# ProDoc_Schematic1_2025-12-06_1.net
KiCad netlist of a schematic drawn in EasyEDA Pro
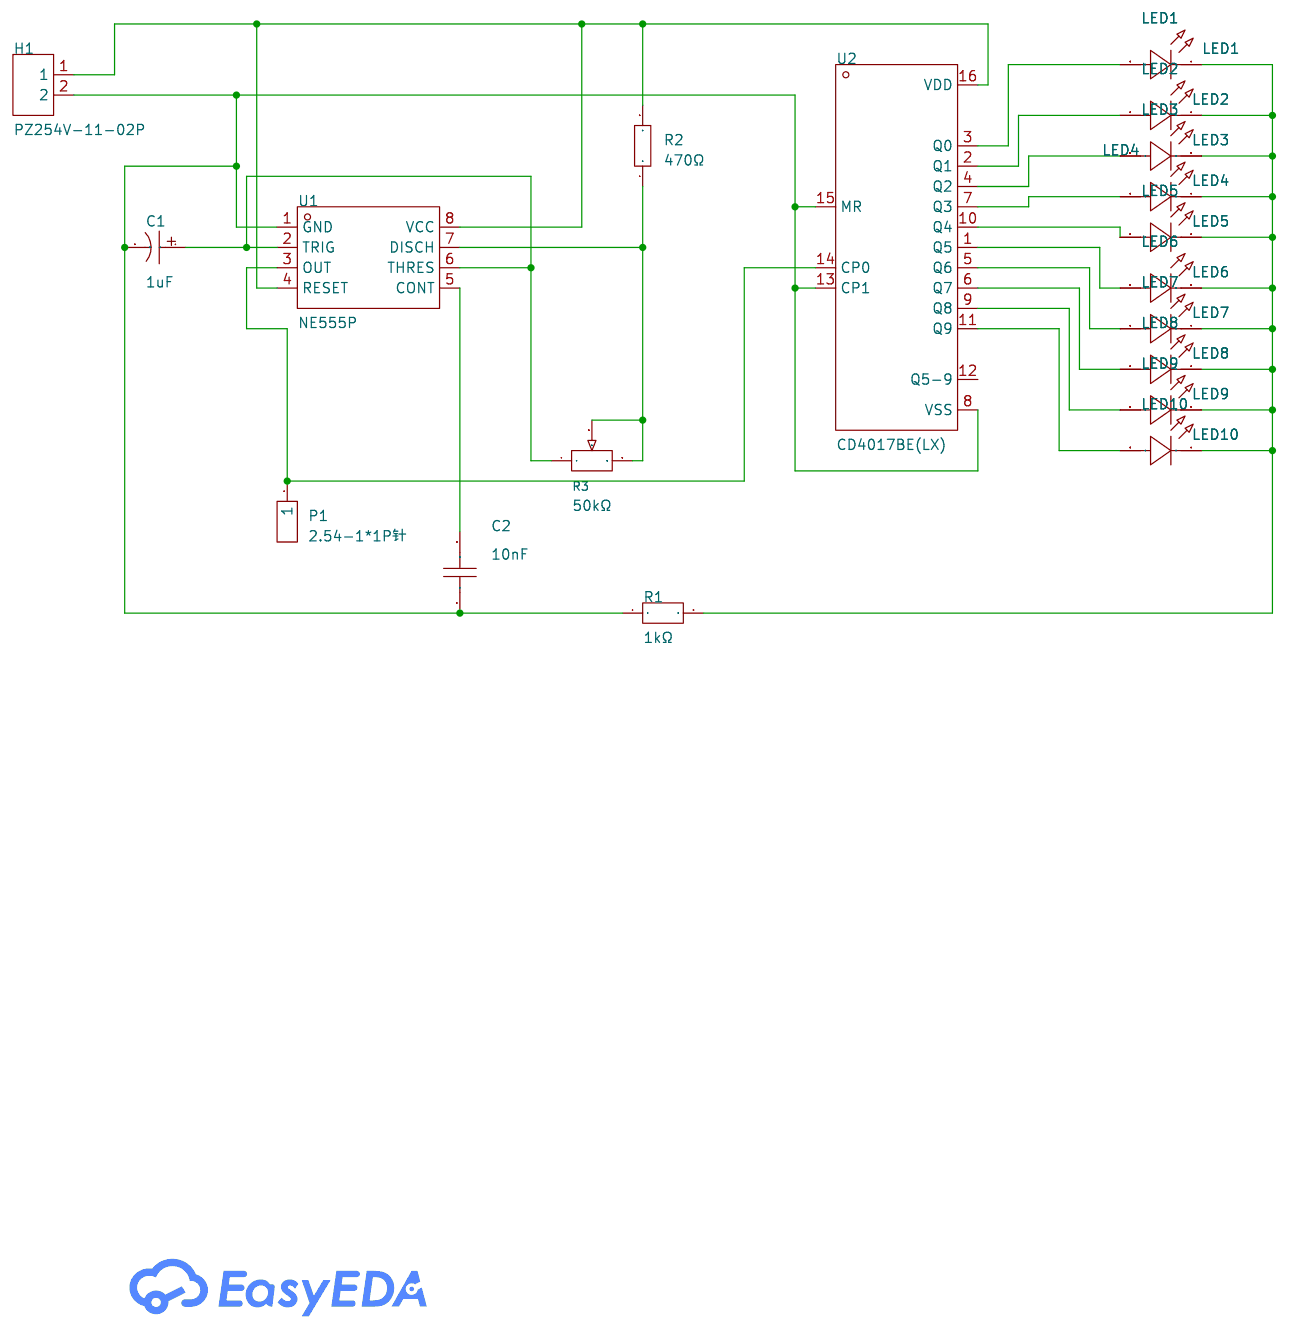
[diagram p0: schematic sheet]

(export (version "E")
  (design (tool "Eeschema 10.0.6"))
  (components
    (comp (ref "C1")
      (value "1uF")
      (footprint "easyedapro:CAP-TH_BD5.0-P2.00-D0.8-FD")
      (fields (field (name "Manufacturer Part") "KF010M050C110A") (field (name "Manufacturer") "CapXon(丰宾)"))
      (libsource (lib "easyedapro") (part "KF010M050C110A"))
    )
    (comp (ref "C2")
      (value "10nF")
      (footprint "easyedapro:CAP-TH_L8.0-W4.0-P5.00-D1.2")
      (fields (field (name "Manufacturer Part") "N09F1B103MN0B0S0N0") (field (name "Manufacturer") "STE(松田)"))
      (libsource (lib "easyedapro") (part "N09F1B103MN0B0S0N0"))
    )
    (comp (ref "H1")
      (value "PZ254V-11-02P")
      (footprint "easyedapro:HDR-TH_2P-P2.54-V-M")
      (fields (field (name "Manufacturer") "XFCN(兴飞)"))
      (libsource (lib "easyedapro") (part "PZ254V-11-02P"))
    )
    (comp (ref "LED1")
      (value "LED1")
      (footprint "easyedapro:LED-TH_BD5.9-P2.54-RD_WHITE")
      (fields (field (name "Manufacturer") "XINGLIGHT(成兴光)"))
      (libsource (lib "easyedapro") (part "XL-502UWC"))
    )
    (comp (ref "LED2")
      (value "LED2")
      (footprint "easyedapro:LED-TH_BD5.9-P2.54-RD_WHITE")
      (fields (field (name "Manufacturer") "XINGLIGHT(成兴光)"))
      (libsource (lib "easyedapro") (part "XL-502UWC"))
    )
    (comp (ref "LED3")
      (value "LED3")
      (footprint "easyedapro:LED-TH_BD5.9-P2.54-RD_WHITE")
      (fields (field (name "Manufacturer") "XINGLIGHT(成兴光)"))
      (libsource (lib "easyedapro") (part "XL-502UWC"))
    )
    (comp (ref "LED4")
      (value "LED4")
      (footprint "easyedapro:LED-TH_BD5.9-P2.54-RD_WHITE")
      (fields (field (name "Manufacturer") "XINGLIGHT(成兴光)"))
      (libsource (lib "easyedapro") (part "XL-502UWC"))
    )
    (comp (ref "LED5")
      (value "LED5")
      (footprint "easyedapro:LED-TH_BD5.9-P2.54-RD_WHITE")
      (fields (field (name "Manufacturer") "XINGLIGHT(成兴光)"))
      (libsource (lib "easyedapro") (part "XL-502UWC"))
    )
    (comp (ref "LED6")
      (value "LED6")
      (footprint "easyedapro:LED-TH_BD5.9-P2.54-RD_WHITE")
      (fields (field (name "Manufacturer") "XINGLIGHT(成兴光)"))
      (libsource (lib "easyedapro") (part "XL-502UWC"))
    )
    (comp (ref "LED7")
      (value "LED7")
      (footprint "easyedapro:LED-TH_BD5.9-P2.54-RD_WHITE")
      (fields (field (name "Manufacturer") "XINGLIGHT(成兴光)"))
      (libsource (lib "easyedapro") (part "XL-502UWC"))
    )
    (comp (ref "LED8")
      (value "LED8")
      (footprint "easyedapro:LED-TH_BD5.9-P2.54-RD_WHITE")
      (fields (field (name "Manufacturer") "XINGLIGHT(成兴光)"))
      (libsource (lib "easyedapro") (part "XL-502UWC"))
    )
    (comp (ref "LED9")
      (value "LED9")
      (footprint "easyedapro:LED-TH_BD5.9-P2.54-RD_WHITE")
      (fields (field (name "Manufacturer") "XINGLIGHT(成兴光)"))
      (libsource (lib "easyedapro") (part "XL-502UWC"))
    )
    (comp (ref "LED10")
      (value "LED10")
      (footprint "easyedapro:LED-TH_BD5.9-P2.54-RD_WHITE")
      (fields (field (name "Manufacturer") "XINGLIGHT(成兴光)"))
      (libsource (lib "easyedapro") (part "XL-502UWC"))
    )
    (comp (ref "P1")
      (value "2.54-1*1P针")
      (footprint "easyedapro:HDR-TH_1P-P2.54-V-M")
      (fields (field (name "Manufacturer") "BOOMELE(博穆精密)"))
      (libsource (lib "easyedapro") (part "Header-Male-2.54_1x1"))
    )
    (comp (ref "R1")
      (value "1kΩ")
      (footprint "easyedapro:RES-TH_BD2.3-L6.5-P10.50-D0.5")
      (fields (field (name "Manufacturer Part") "MF1/4W-1KΩ±1%T52") (field (name "Manufacturer") "华星机电"))
      (libsource (lib "easyedapro") (part "MF1/4W-1KΩ±1%T52"))
    )
    (comp (ref "R2")
      (value "470Ω")
      (footprint "easyedapro:RES-TH_BD2.2-L6.5-P10.50-D0.6")
      (fields
        (field (name "Manufacturer Part") "MFR0W4F4700A50")
        (field (name "Manufacturer") "UNI-ROYAL(厚声)")
      )
      (libsource (lib "easyedapro") (part "MFR0W4F4700A50"))
    )
    (comp (ref "R3")
      (value "50kΩ")
      (footprint "easyedapro:RES-ADJ-TH_3P-L9.5-W4.85-P2.50-BL-L")
      (fields (field (name "Manufacturer Part") "3296X-1-503") (field (name "Manufacturer") "BOCHEN(博晨)"))
      (libsource (lib "easyedapro") (part "3296X-1-503_C118912"))
    )
    (comp (ref "U1")
      (value "NE555P")
      (footprint "easyedapro:DIP-8_L9.8-W6.6-P2.54-LS7.6-BL")
      (fields (field (name "Manufacturer") "TI(德州仪器)"))
      (libsource (lib "easyedapro") (part "NE555P"))
    )
    (comp (ref "U2")
      (value "CD4017BE(LX)")
      (footprint "easyedapro:PDIP-16_L19.3-W6.4-P2.54-LS7.94-BL")
      (fields (field (name "Manufacturer") "LX(灵星芯微)"))
      (libsource (lib "easyedapro") (part "CD4017BE(LX)"))
    )
  )
  (nets
    (net (code "1") (name "Net-(LED1-A)") (class "Default")
      (node (ref "LED1") (pin "2") (pinfunction "A_2") (pintype "unspecified"))
      (node (ref "U2") (pin "3") (pinfunction "Q0_3") (pintype "unspecified"))
    )
    (net (code "2") (name "Net-(LED1-K)") (class "Default")
      (node (ref "LED1") (pin "1") (pinfunction "K_1") (pintype "unspecified"))
      (node (ref "LED10") (pin "1") (pinfunction "K_1") (pintype "unspecified"))
      (node (ref "LED2") (pin "1") (pinfunction "K_1") (pintype "unspecified"))
      (node (ref "LED3") (pin "1") (pinfunction "K_1") (pintype "unspecified"))
      (node (ref "LED4") (pin "1") (pinfunction "K_1") (pintype "unspecified"))
      (node (ref "LED5") (pin "1") (pinfunction "K_1") (pintype "unspecified"))
      (node (ref "LED6") (pin "1") (pinfunction "K_1") (pintype "unspecified"))
      (node (ref "LED7") (pin "1") (pinfunction "K_1") (pintype "unspecified"))
      (node (ref "LED8") (pin "1") (pinfunction "K_1") (pintype "unspecified"))
      (node (ref "LED9") (pin "1") (pinfunction "K_1") (pintype "unspecified"))
      (node (ref "R1") (pin "2") (pinfunction "2_2") (pintype "unspecified"))
    )
    (net (code "3") (name "Net-(LED2-A)") (class "Default")
      (node (ref "LED2") (pin "2") (pinfunction "A_2") (pintype "unspecified"))
      (node (ref "U2") (pin "2") (pinfunction "Q1_2") (pintype "unspecified"))
    )
    (net (code "4") (name "Net-(LED3-A)") (class "Default")
      (node (ref "LED3") (pin "2") (pinfunction "A_2") (pintype "unspecified"))
      (node (ref "U2") (pin "4") (pinfunction "Q2_4") (pintype "unspecified"))
    )
    (net (code "5") (name "Net-(LED4-A)") (class "Default")
      (node (ref "LED4") (pin "2") (pinfunction "A_2") (pintype "unspecified"))
      (node (ref "U2") (pin "7") (pinfunction "Q3_7") (pintype "unspecified"))
    )
    (net (code "6") (name "Net-(LED5-A)") (class "Default")
      (node (ref "LED5") (pin "2") (pinfunction "A_2") (pintype "unspecified"))
      (node (ref "U2") (pin "10") (pinfunction "Q4_10") (pintype "unspecified"))
    )
    (net (code "7") (name "Net-(LED6-A)") (class "Default")
      (node (ref "LED6") (pin "2") (pinfunction "A_2") (pintype "unspecified"))
      (node (ref "U2") (pin "1") (pinfunction "Q5_1") (pintype "unspecified"))
    )
    (net (code "8") (name "Net-(LED7-A)") (class "Default")
      (node (ref "LED7") (pin "2") (pinfunction "A_2") (pintype "unspecified"))
      (node (ref "U2") (pin "5") (pinfunction "Q6_5") (pintype "unspecified"))
    )
    (net (code "9") (name "Net-(LED8-A)") (class "Default")
      (node (ref "LED8") (pin "2") (pinfunction "A_2") (pintype "unspecified"))
      (node (ref "U2") (pin "6") (pinfunction "Q7_6") (pintype "unspecified"))
    )
    (net (code "10") (name "Net-(LED9-A)") (class "Default")
      (node (ref "LED9") (pin "2") (pinfunction "A_2") (pintype "unspecified"))
      (node (ref "U2") (pin "9") (pinfunction "Q8_9") (pintype "unspecified"))
    )
    (net (code "11") (name "Net-(LED10-A)") (class "Default")
      (node (ref "LED10") (pin "2") (pinfunction "A_2") (pintype "unspecified"))
      (node (ref "U2") (pin "11") (pinfunction "Q9_11") (pintype "unspecified"))
    )
    (net (code "12") (name "Net-(U1-CONT)") (class "Default")
      (node (ref "C2") (pin "2") (pinfunction "2_2") (pintype "unspecified"))
      (node (ref "U1") (pin "5") (pinfunction "CONT_5") (pintype "input"))
    )
    (net (code "13") (name "Net-(U1-DISCH)") (class "Default")
      (node (ref "R2") (pin "1") (pinfunction "1_1") (pintype "input"))
      (node (ref "R3") (pin "2") (pinfunction "2_2") (pintype "input"))
      (node (ref "R3") (pin "3") (pinfunction "3_3") (pintype "input"))
      (node (ref "U1") (pin "7") (pinfunction "DISCH_7") (pintype "input"))
    )
    (net (code "14") (name "Net-(U1-GND)") (class "Default")
      (node (ref "C1") (pin "2") (pinfunction "2_2") (pintype "input"))
      (node (ref "C2") (pin "1") (pinfunction "1_1") (pintype "unspecified"))
      (node (ref "H1") (pin "2") (pinfunction "2_2") (pintype "unspecified"))
      (node (ref "R1") (pin "1") (pinfunction "1_1") (pintype "unspecified"))
      (node (ref "U1") (pin "1") (pinfunction "GND_1") (pintype "input"))
      (node (ref "U2") (pin "13") (pinfunction "CP1_13") (pintype "unspecified"))
      (node (ref "U2") (pin "15") (pinfunction "MR_15") (pintype "unspecified"))
      (node (ref "U2") (pin "8") (pinfunction "VSS_8") (pintype "unspecified"))
    )
    (net (code "15") (name "Net-(U1-OUT)") (class "Default")
      (node (ref "P1") (pin "1") (pinfunction "1_1") (pintype "input"))
      (node (ref "U1") (pin "3") (pinfunction "OUT_3") (pintype "input"))
      (node (ref "U2") (pin "14") (pinfunction "CP0_14") (pintype "unspecified"))
    )
    (net (code "16") (name "Net-(U1-RESET)") (class "Default")
      (node (ref "H1") (pin "1") (pinfunction "1_1") (pintype "unspecified"))
      (node (ref "R2") (pin "2") (pinfunction "2_2") (pintype "input"))
      (node (ref "U1") (pin "4") (pinfunction "RESET_4") (pintype "input"))
      (node (ref "U1") (pin "8") (pinfunction "VCC_8") (pintype "input"))
      (node (ref "U2") (pin "16") (pinfunction "VDD_16") (pintype "unspecified"))
    )
    (net (code "17") (name "Net-(U1-THRES)") (class "Default")
      (node (ref "C1") (pin "1") (pinfunction "1_1") (pintype "input"))
      (node (ref "R3") (pin "1") (pinfunction "1_1") (pintype "input"))
      (node (ref "U1") (pin "2") (pinfunction "TRIG_2") (pintype "input"))
      (node (ref "U1") (pin "6") (pinfunction "THRES_6") (pintype "input"))
    )
    (net (code "18") (name "unconnected-(U2-Q5-9-Pad12)") (class "Default")
      (node (ref "U2") (pin "12") (pinfunction "Q5-9_12") (pintype "unspecified"))
    )
  )
)
